# suply_1w.net
KiCad netlist of a schematic drawn in Altium Designer
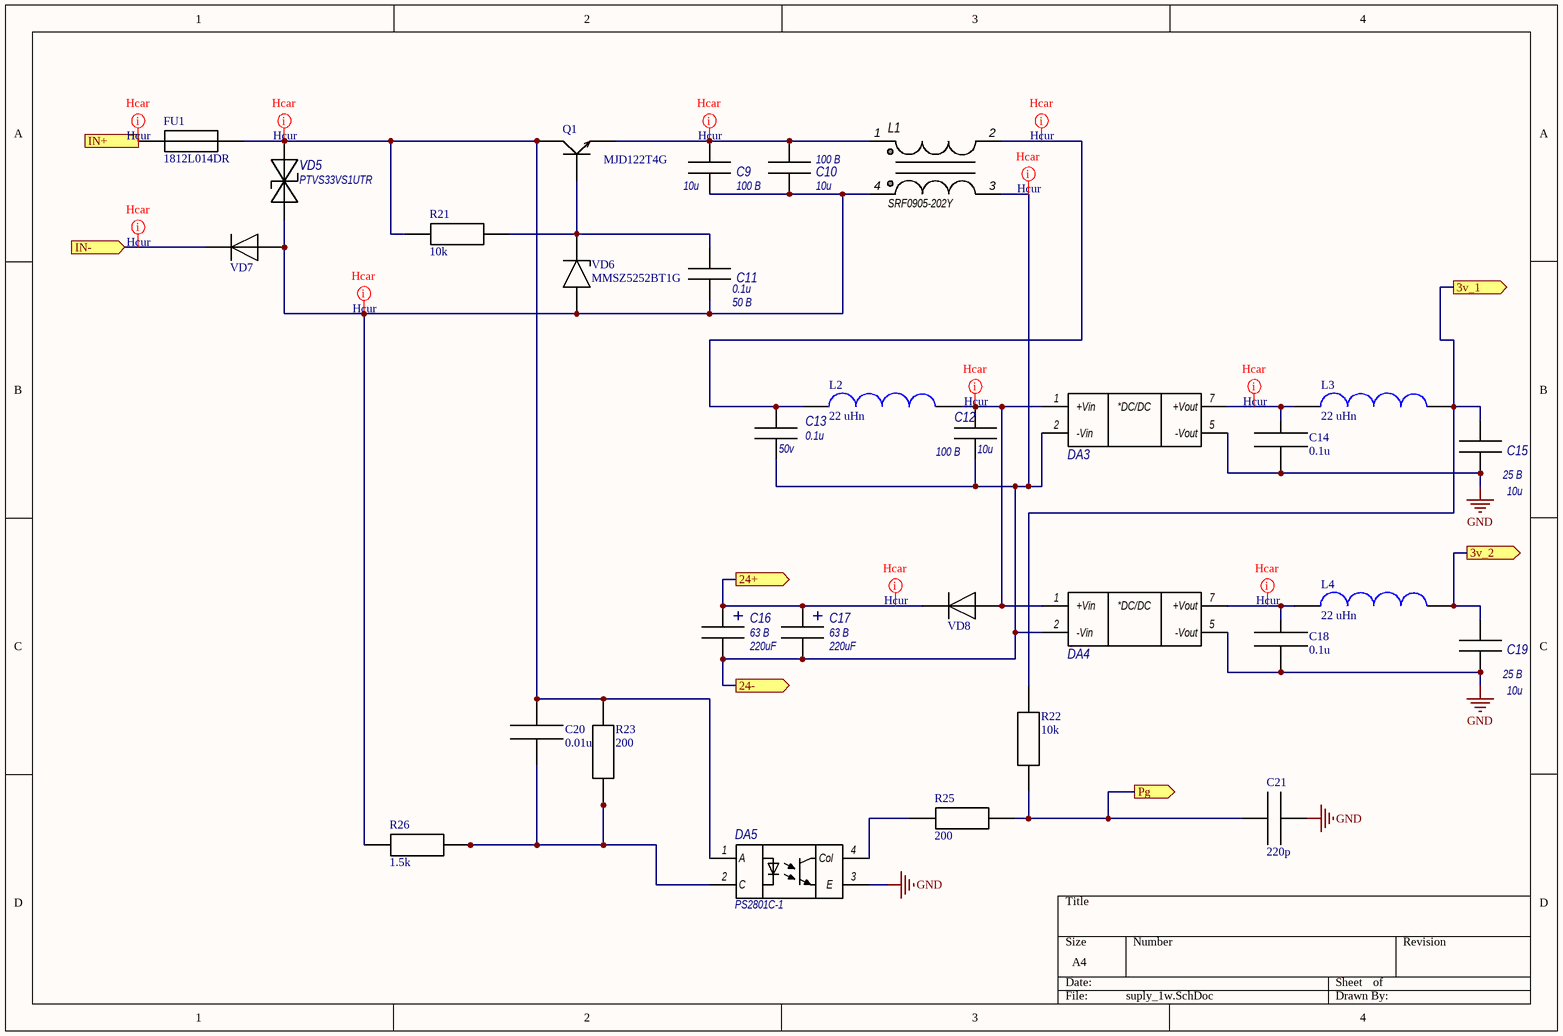
[diagram p0: suply_1w.SchDoc]

(export (version "E")
  (design (tool "Eeschema 10.0.6"))
  (components
    (comp (ref "C9")
      (value "10u")
      (footprint "C1206_")
      (fields (field (name "VOLTAGE") "100 В") (field (name "Comment") "10u 100v"))
      (libsource (lib "altium-import") (part "root_1_Capacitor ceramic_"))
    )
    (comp (ref "C10")
      (value "10u")
      (footprint "C1206_")
      (fields (field (name "VOLTAGE") "100 В") (field (name "Comment") "10u 100v"))
      (libsource (lib "altium-import") (part "root_1_Capacitor ceramic_"))
    )
    (comp (ref "C11")
      (value "0.1u")
      (footprint "C0603")
      (fields (field (name "VOLTAGE") "50 В"))
      (libsource (lib "altium-import") (part "root_1_Capacitor ceramic_"))
    )
    (comp (ref "C12")
      (value "10u")
      (footprint "C1206_")
      (fields (field (name "VOLTAGE") "100 В") (field (name "Comment") "10u 100v"))
      (libsource (lib "altium-import") (part "root_1_Capacitor ceramic_"))
    )
    (comp (ref "C13")
      (value "0.1u")
      (footprint "C0603")
      (fields (field (name "VOLTAGE") "50v"))
      (libsource (lib "altium-import") (part "root_1_Capacitor ceramic_"))
    )
    (comp (ref "C14") (value "0.1u") (footprint "cap_0402") (libsource (lib "lib") (part "cap")))
    (comp (ref "C15")
      (value "10u")
      (footprint "C0603")
      (fields (field (name "VOLTAGE") "25 В"))
      (libsource (lib "altium-import") (part "root_1_Capacitor ceramic_"))
    )
    (comp (ref "C16")
      (value "220uF")
      (footprint "rad_cap_10х12")
      (fields
        (field (name "TOLERANCE") "±20%")
        (field (name "VOLTAGE") "63 В")
        (field (name "Comment") "220u 63v")
      )
      (libsource (lib "pre_CAPACITOR") (part "Capacitor electrolytic"))
    )
    (comp (ref "C17")
      (value "220uF")
      (footprint "rad_cap_10х12")
      (description "10x12")
      (fields
        (field (name "TOLERANCE") "±20%")
        (field (name "VOLTAGE") "63 В")
        (field (name "Comment") "220u 63v")
      )
      (libsource (lib "pre_CAPACITOR") (part "Capacitor electrolytic"))
    )
    (comp (ref "C18") (value "0.1u") (footprint "cap_0402") (libsource (lib "lib") (part "cap")))
    (comp (ref "C19")
      (value "10u")
      (footprint "C0603")
      (fields (field (name "VOLTAGE") "25 В"))
      (libsource (lib "altium-import") (part "root_1_Capacitor ceramic_"))
    )
    (comp (ref "C20") (value "0.01u") (footprint "0603_cap") (libsource (lib "lib") (part "cap")))
    (comp (ref "C21") (value "220p") (footprint "cap_0402") (libsource (lib "lib") (part "cap")))
    (comp (ref "DA3")
      (value "AM1D-2403SH30Z")
      (footprint "AM1D-2405")
      (description "AM1D-2403SH30Z 21.6-26.4V 3.3V 200mA 3000V 54мА 6мА 220мкF 77%")
      (libsource (lib "lib") (part "AM1D-2405SH30Z"))
    )
    (comp (ref "DA4")
      (value "AM1D-2403SH30Z")
      (footprint "AM1D-2405")
      (description "AM1D-2403SH30Z 21.6-26.4V 3.3V 200mA 3000V 54мА 6мА 220мкF 77%")
      (libsource (lib "lib") (part "AM1D-2405SH30Z"))
    )
    (comp (ref "DA5")
      (value "PS2801C-1")
      (footprint "SSOP-4N")
      (fields (field (name "TYPE") "PS2801C-1"))
      (libsource (lib "Optocoupler") (part "PS2801C-1"))
    )
    (comp (ref "FU1") (value "1812L014DR") (footprint "fuse1210") (libsource (lib "lib") (part "fuse")))
    (comp (ref "L1")
      (value "SRF0905-202Y")
      (footprint "SRF0905")
      (fields (field (name "Comment") "SRF0905"))
      (libsource (lib "altium-import") (part "root_0_SRF0905_"))
    )
    (comp (ref "L2") (value "22 uHn") (footprint "ifsc1515") (libsource (lib "lib") (part "ind_b82477g4")))
    (comp (ref "L3") (value "22 uHn") (footprint "ifsc1515") (libsource (lib "lib") (part "ind_b82477g4")))
    (comp (ref "L4") (value "22 uHn") (footprint "ifsc1515") (libsource (lib "lib") (part "ind_b82477g4")))
    (comp (ref "Q1") (value "MJD122T4G") (footprint "sot23") (libsource (lib "lib") (part "npn")))
    (comp (ref "R21") (value "10k") (footprint "0603_res") (libsource (lib "lib") (part "res")))
    (comp (ref "R22") (value "10k") (footprint "res_0402") (libsource (lib "lib") (part "res")))
    (comp (ref "R23") (value "200") (footprint "0603_res") (libsource (lib "lib") (part "res")))
    (comp (ref "R25") (value "200") (footprint "res_0402") (libsource (lib "lib") (part "res")))
    (comp (ref "R26") (value "1.5k") (footprint "2512_res") (libsource (lib "lib") (part "res")))
    (comp (ref "VD5")
      (value "PTVS33VS1UTR")
      (footprint "SOD-123")
      (description "PTVS33VS1UTR,115, TVS DIODE 33VWM 53.3VC SOD123W")
      (fields (field (name "TYPE") "PTVS33VS1UTR"))
      (libsource (lib "lib") (part "PTVS33VS1UTR"))
    )
    (comp (ref "VD6")
      (value "MMSZ5252BT1G")
      (footprint "SOD-123")
      (description "MMSZ5252BT1G, Стабилитрон 0.5Вт 24В")
      (libsource (lib "lib") (part "stab"))
    )
    (comp (ref "VD7") (value "1N4448W") (footprint "SOD-123") (libsource (lib "lib") (part "1N4448")))
    (comp (ref "VD8") (value "1N4448W") (footprint "SOD-123") (libsource (lib "lib") (part "1N4448")))
  )
  (nets
    (net (code "1") (name "/3v_1") (class "Default")
      (node (ref "C15") (pin "2") (pinfunction "2_2") (pintype "passive"))
      (node (ref "L3") (pin "2") (pinfunction "2_2") (pintype "passive"))
      (node (ref "R22") (pin "2") (pinfunction "2_2") (pintype "passive"))
    )
    (net (code "2") (name "/3v_2") (class "Default")
      (node (ref "C19") (pin "2") (pinfunction "2_2") (pintype "passive"))
      (node (ref "L4") (pin "2") (pinfunction "2_2") (pintype "passive"))
    )
    (net (code "3") (name "/24+") (class "Default")
      (node (ref "C16") (pin "1") (pinfunction "A_1") (pintype "passive"))
      (node (ref "C17") (pin "1") (pinfunction "A_1") (pintype "passive"))
      (node (ref "VD8") (pin "K") (pinfunction "K_K") (pintype "passive"))
    )
    (net (code "4") (name "/24-") (class "Default")
      (node (ref "C12") (pin "1") (pinfunction "1_1") (pintype "passive"))
      (node (ref "C13") (pin "1") (pinfunction "1_1") (pintype "passive"))
      (node (ref "C16") (pin "2") (pinfunction "K_2") (pintype "passive"))
      (node (ref "C17") (pin "2") (pinfunction "K_2") (pintype "passive"))
      (node (ref "DA3") (pin "2") (pinfunction "-Vin_2") (pintype "power_in"))
      (node (ref "DA4") (pin "2") (pinfunction "-Vin_2") (pintype "power_in"))
      (node (ref "L1") (pin "3") (pinfunction "3_3") (pintype "passive"))
    )
    (net (code "5") (name "/IN+") (class "Default")
      (node (ref "FU1") (pin "1") (pinfunction "1_1") (pintype "passive"))
    )
    (net (code "6") (name "/IN-") (class "Default")
      (node (ref "VD7") (pin "K") (pinfunction "K_K") (pintype "passive"))
    )
    (net (code "7") (name "/Pg") (class "Default")
      (node (ref "C21") (pin "2") (pinfunction "2_2") (pintype "passive"))
      (node (ref "R22") (pin "1") (pinfunction "1_1") (pintype "passive"))
      (node (ref "R25") (pin "1") (pinfunction "1_1") (pintype "passive"))
    )
    (net (code "8") (name "GND") (class "Default")
      (node (ref "C14") (pin "2") (pinfunction "2_2") (pintype "passive"))
      (node (ref "C15") (pin "1") (pinfunction "1_1") (pintype "passive"))
      (node (ref "C18") (pin "2") (pinfunction "2_2") (pintype "passive"))
      (node (ref "C19") (pin "1") (pinfunction "1_1") (pintype "passive"))
      (node (ref "C21") (pin "1") (pinfunction "1_1") (pintype "passive"))
      (node (ref "DA3") (pin "5") (pinfunction "-Vout_5") (pintype "power_in"))
      (node (ref "DA4") (pin "5") (pinfunction "-Vout_5") (pintype "power_in"))
      (node (ref "DA5") (pin "3") (pinfunction "E_3") (pintype "passive"))
    )
    (net (code "9") (name "Net-(C10-Pad1)") (class "Default")
      (node (ref "C10") (pin "1") (pinfunction "1_1") (pintype "passive"))
      (node (ref "C11") (pin "1") (pinfunction "1_1") (pintype "passive"))
      (node (ref "C9") (pin "1") (pinfunction "1_1") (pintype "passive"))
      (node (ref "L1") (pin "4") (pinfunction "4_4") (pintype "passive"))
      (node (ref "R26") (pin "1") (pinfunction "1_1") (pintype "passive"))
      (node (ref "VD5") (pin "A") (pinfunction "A_A") (pintype "passive"))
      (node (ref "VD6") (pin "A") (pinfunction "A_A") (pintype "passive"))
      (node (ref "VD7") (pin "A") (pinfunction "A_A") (pintype "passive"))
    )
    (net (code "10") (name "Net-(C13-Pad2)") (class "Default")
      (node (ref "C13") (pin "2") (pinfunction "2_2") (pintype "passive"))
      (node (ref "L1") (pin "2") (pinfunction "2_2") (pintype "passive"))
      (node (ref "L2") (pin "1") (pinfunction "1_1") (pintype "passive"))
    )
    (net (code "11") (name "Net-(DA3-+Vin)") (class "Default")
      (node (ref "C12") (pin "2") (pinfunction "2_2") (pintype "passive"))
      (node (ref "DA3") (pin "1") (pinfunction "+Vin_1") (pintype "power_in"))
      (node (ref "DA4") (pin "1") (pinfunction "+Vin_1") (pintype "power_in"))
      (node (ref "L2") (pin "2") (pinfunction "2_2") (pintype "passive"))
      (node (ref "VD8") (pin "A") (pinfunction "A_A") (pintype "passive"))
    )
    (net (code "12") (name "Net-(DA3-+Vout)") (class "Default")
      (node (ref "C14") (pin "1") (pinfunction "1_1") (pintype "passive"))
      (node (ref "DA3") (pin "7") (pinfunction "+Vout_7") (pintype "power_in"))
      (node (ref "L3") (pin "1") (pinfunction "1_1") (pintype "passive"))
    )
    (net (code "13") (name "Net-(DA4-+Vout)") (class "Default")
      (node (ref "C18") (pin "1") (pinfunction "1_1") (pintype "passive"))
      (node (ref "DA4") (pin "7") (pinfunction "+Vout_7") (pintype "power_in"))
      (node (ref "L4") (pin "1") (pinfunction "1_1") (pintype "passive"))
    )
    (net (code "14") (name "Net-(DA5-A)") (class "Default")
      (node (ref "C20") (pin "2") (pinfunction "2_2") (pintype "passive"))
      (node (ref "DA5") (pin "1") (pinfunction "A_1") (pintype "passive"))
      (node (ref "FU1") (pin "2") (pinfunction "2_2") (pintype "passive"))
      (node (ref "Q1") (pin "2") (pinfunction "K_2") (pintype "passive"))
      (node (ref "R21") (pin "1") (pinfunction "1_1") (pintype "passive"))
      (node (ref "R23") (pin "2") (pinfunction "2_2") (pintype "passive"))
      (node (ref "VD5") (pin "K") (pinfunction "K_K") (pintype "passive"))
    )
    (net (code "15") (name "Net-(DA5-C)") (class "Default")
      (node (ref "C20") (pin "1") (pinfunction "1_1") (pintype "passive"))
      (node (ref "DA5") (pin "2") (pinfunction "C_2") (pintype "passive"))
      (node (ref "R23") (pin "1") (pinfunction "1_1") (pintype "passive"))
      (node (ref "R26") (pin "2") (pinfunction "2_2") (pintype "passive"))
    )
    (net (code "16") (name "Net-(DA5-Col)") (class "Default")
      (node (ref "DA5") (pin "4") (pinfunction "Col_4") (pintype "passive"))
      (node (ref "R25") (pin "2") (pinfunction "2_2") (pintype "passive"))
    )
    (net (code "17") (name "Net-(Q1-B)") (class "Default")
      (node (ref "C11") (pin "2") (pinfunction "2_2") (pintype "passive"))
      (node (ref "Q1") (pin "1") (pinfunction "B_1") (pintype "passive"))
      (node (ref "R21") (pin "2") (pinfunction "2_2") (pintype "passive"))
      (node (ref "VD6") (pin "K") (pinfunction "K_K") (pintype "passive"))
    )
    (net (code "18") (name "Net-(Q1-E)") (class "Default")
      (node (ref "C10") (pin "2") (pinfunction "2_2") (pintype "passive"))
      (node (ref "C9") (pin "2") (pinfunction "2_2") (pintype "passive"))
      (node (ref "L1") (pin "1") (pinfunction "1_1") (pintype "passive"))
      (node (ref "Q1") (pin "3") (pinfunction "E_3") (pintype "passive"))
    )
  )
)
